# ENC_BOARD_V01.net
KiCad netlist of a schematic drawn in EAGLE
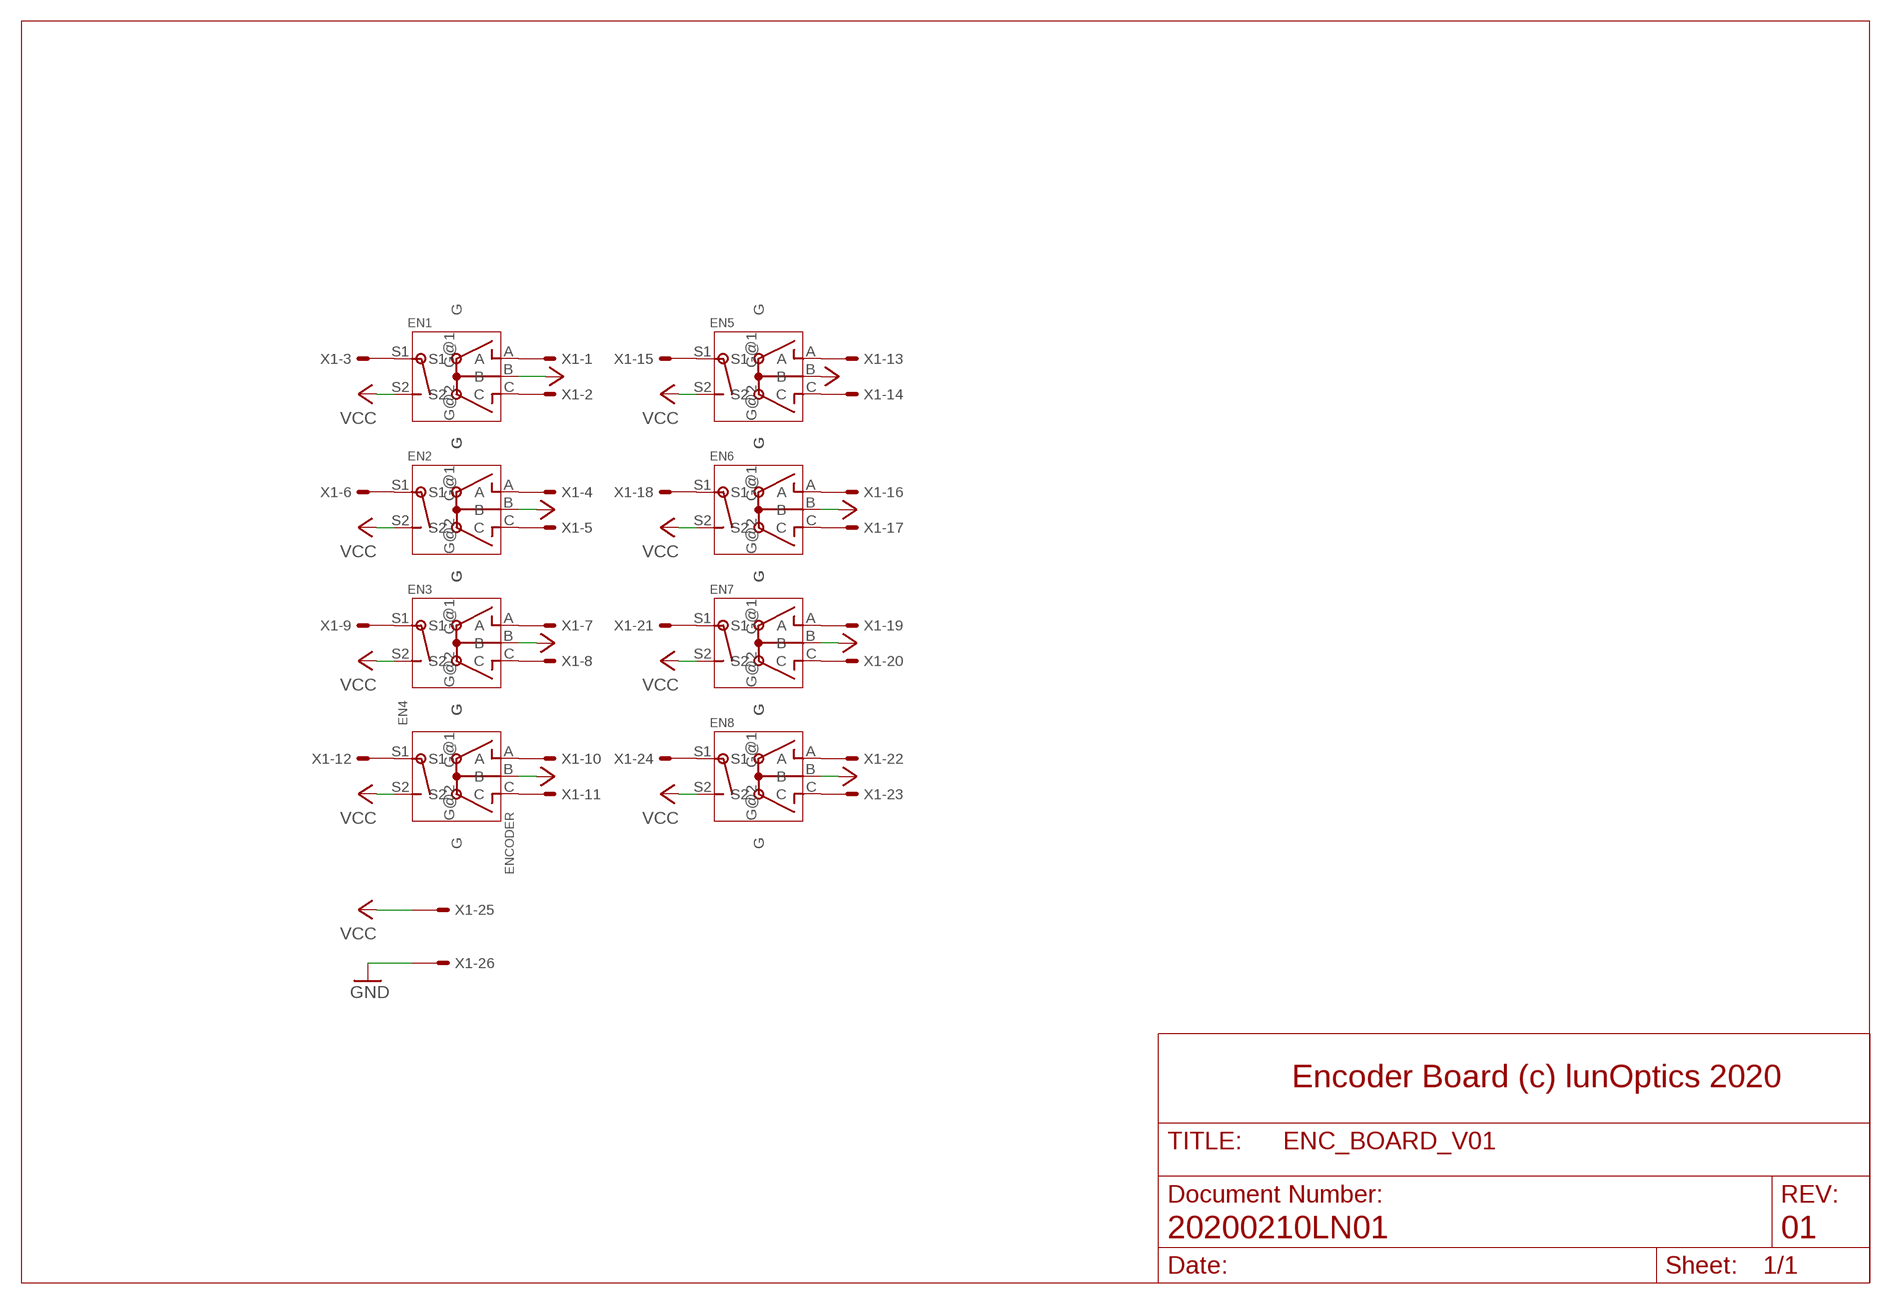
[diagram p0: schematic, sheet 1]

(export (version "E")
  (design (tool "Eeschema 10.0.6"))
  (components
    (comp (ref "EN1")
      (value "ENCODER")
      (footprint "eagle-import:ENCODER")
      (libsource (lib "eagle-import") (part "ENCODER"))
    )
    (comp (ref "EN2")
      (value "ENCODER")
      (footprint "eagle-import:ENCODER")
      (libsource (lib "eagle-import") (part "ENCODER"))
    )
    (comp (ref "EN3")
      (value "ENCODER")
      (footprint "eagle-import:ENCODER")
      (libsource (lib "eagle-import") (part "ENCODER"))
    )
    (comp (ref "EN4")
      (value "ENCODER")
      (footprint "eagle-import:ENCODER")
      (libsource (lib "eagle-import") (part "ENCODER"))
    )
    (comp (ref "EN5")
      (value "ENCODER")
      (footprint "eagle-import:ENCODER")
      (libsource (lib "eagle-import") (part "ENCODER"))
    )
    (comp (ref "EN6")
      (value "ENCODER")
      (footprint "eagle-import:ENCODER")
      (libsource (lib "eagle-import") (part "ENCODER"))
    )
    (comp (ref "EN7")
      (value "ENCODER")
      (footprint "eagle-import:ENCODER")
      (libsource (lib "eagle-import") (part "ENCODER"))
    )
    (comp (ref "EN8")
      (value "ENCODER")
      (footprint "eagle-import:ENCODER")
      (libsource (lib "eagle-import") (part "ENCODER"))
    )
    (comp (ref "X1")
      (value "057-026-1")
      (footprint "eagle-import:057-026-1")
      (libsource (lib "eagle-import") (part "057-026-1"))
    )
  )
  (nets
    (net (code "1") (name "GND") (class "Default")
      (node (ref "X1") (pin "26") (pinfunction "S_26") (pintype "passive"))
    )
    (net (code "2") (name "Net-(X1A-S)") (class "Default")
      (node (ref "EN1") (pin "A") (pinfunction "A_A") (pintype "passive"))
      (node (ref "X1") (pin "1") (pinfunction "S_1") (pintype "passive"))
    )
    (net (code "3") (name "Net-(X1B-S)") (class "Default")
      (node (ref "EN4") (pin "A") (pinfunction "A_A") (pintype "passive"))
      (node (ref "X1") (pin "10") (pinfunction "S_10") (pintype "passive"))
    )
    (net (code "4") (name "Net-(X1C-S)") (class "Default")
      (node (ref "EN4") (pin "C") (pinfunction "C_C") (pintype "passive"))
      (node (ref "X1") (pin "11") (pinfunction "S_11") (pintype "passive"))
    )
    (net (code "5") (name "Net-(X1D-S)") (class "Default")
      (node (ref "EN4") (pin "S1") (pinfunction "S1_S1") (pintype "passive"))
      (node (ref "X1") (pin "12") (pinfunction "S_12") (pintype "passive"))
    )
    (net (code "6") (name "Net-(X1E-S)") (class "Default")
      (node (ref "EN5") (pin "A") (pinfunction "A_A") (pintype "passive"))
      (node (ref "X1") (pin "13") (pinfunction "S_13") (pintype "passive"))
    )
    (net (code "7") (name "Net-(X1F-S)") (class "Default")
      (node (ref "EN5") (pin "C") (pinfunction "C_C") (pintype "passive"))
      (node (ref "X1") (pin "14") (pinfunction "S_14") (pintype "passive"))
    )
    (net (code "8") (name "Net-(X1G-S)") (class "Default")
      (node (ref "EN5") (pin "S1") (pinfunction "S1_S1") (pintype "passive"))
      (node (ref "X1") (pin "15") (pinfunction "S_15") (pintype "passive"))
    )
    (net (code "9") (name "Net-(X1H-S)") (class "Default")
      (node (ref "EN6") (pin "A") (pinfunction "A_A") (pintype "passive"))
      (node (ref "X1") (pin "16") (pinfunction "S_16") (pintype "passive"))
    )
    (net (code "10") (name "Net-(X1I-S)") (class "Default")
      (node (ref "EN6") (pin "C") (pinfunction "C_C") (pintype "passive"))
      (node (ref "X1") (pin "17") (pinfunction "S_17") (pintype "passive"))
    )
    (net (code "11") (name "Net-(X1J-S)") (class "Default")
      (node (ref "EN6") (pin "S1") (pinfunction "S1_S1") (pintype "passive"))
      (node (ref "X1") (pin "18") (pinfunction "S_18") (pintype "passive"))
    )
    (net (code "12") (name "Net-(X1K-S)") (class "Default")
      (node (ref "EN7") (pin "A") (pinfunction "A_A") (pintype "passive"))
      (node (ref "X1") (pin "19") (pinfunction "S_19") (pintype "passive"))
    )
    (net (code "13") (name "Net-(X1L-S)") (class "Default")
      (node (ref "EN1") (pin "C") (pinfunction "C_C") (pintype "passive"))
      (node (ref "X1") (pin "2") (pinfunction "S_2") (pintype "passive"))
    )
    (net (code "14") (name "Net-(X1M-S)") (class "Default")
      (node (ref "EN7") (pin "C") (pinfunction "C_C") (pintype "passive"))
      (node (ref "X1") (pin "20") (pinfunction "S_20") (pintype "passive"))
    )
    (net (code "15") (name "Net-(X1N-S)") (class "Default")
      (node (ref "EN7") (pin "S1") (pinfunction "S1_S1") (pintype "passive"))
      (node (ref "X1") (pin "21") (pinfunction "S_21") (pintype "passive"))
    )
    (net (code "16") (name "Net-(X1O-S)") (class "Default")
      (node (ref "EN8") (pin "A") (pinfunction "A_A") (pintype "passive"))
      (node (ref "X1") (pin "22") (pinfunction "S_22") (pintype "passive"))
    )
    (net (code "17") (name "Net-(X1P-S)") (class "Default")
      (node (ref "EN8") (pin "C") (pinfunction "C_C") (pintype "passive"))
      (node (ref "X1") (pin "23") (pinfunction "S_23") (pintype "passive"))
    )
    (net (code "18") (name "Net-(X1Q-S)") (class "Default")
      (node (ref "EN8") (pin "S1") (pinfunction "S1_S1") (pintype "passive"))
      (node (ref "X1") (pin "24") (pinfunction "S_24") (pintype "passive"))
    )
    (net (code "19") (name "Net-(X1T-S)") (class "Default")
      (node (ref "EN1") (pin "S1") (pinfunction "S1_S1") (pintype "passive"))
      (node (ref "X1") (pin "3") (pinfunction "S_3") (pintype "passive"))
    )
    (net (code "20") (name "Net-(X1U-S)") (class "Default")
      (node (ref "EN2") (pin "A") (pinfunction "A_A") (pintype "passive"))
      (node (ref "X1") (pin "4") (pinfunction "S_4") (pintype "passive"))
    )
    (net (code "21") (name "Net-(X1V-S)") (class "Default")
      (node (ref "EN2") (pin "C") (pinfunction "C_C") (pintype "passive"))
      (node (ref "X1") (pin "5") (pinfunction "S_5") (pintype "passive"))
    )
    (net (code "22") (name "Net-(X1W-S)") (class "Default")
      (node (ref "EN2") (pin "S1") (pinfunction "S1_S1") (pintype "passive"))
      (node (ref "X1") (pin "6") (pinfunction "S_6") (pintype "passive"))
    )
    (net (code "23") (name "Net-(X1X-S)") (class "Default")
      (node (ref "EN3") (pin "A") (pinfunction "A_A") (pintype "passive"))
      (node (ref "X1") (pin "7") (pinfunction "S_7") (pintype "passive"))
    )
    (net (code "24") (name "Net-(X1Y-S)") (class "Default")
      (node (ref "EN3") (pin "C") (pinfunction "C_C") (pintype "passive"))
      (node (ref "X1") (pin "8") (pinfunction "S_8") (pintype "passive"))
    )
    (net (code "25") (name "Net-(X1Z-S)") (class "Default")
      (node (ref "EN3") (pin "S1") (pinfunction "S1_S1") (pintype "passive"))
      (node (ref "X1") (pin "9") (pinfunction "S_9") (pintype "passive"))
    )
    (net (code "26") (name "VCC") (class "Default")
      (node (ref "EN1") (pin "B") (pinfunction "B_B") (pintype "passive"))
      (node (ref "EN1") (pin "S2") (pinfunction "S2_S2") (pintype "passive"))
      (node (ref "EN2") (pin "B") (pinfunction "B_B") (pintype "passive"))
      (node (ref "EN2") (pin "S2") (pinfunction "S2_S2") (pintype "passive"))
      (node (ref "EN3") (pin "B") (pinfunction "B_B") (pintype "passive"))
      (node (ref "EN3") (pin "S2") (pinfunction "S2_S2") (pintype "passive"))
      (node (ref "EN4") (pin "B") (pinfunction "B_B") (pintype "passive"))
      (node (ref "EN4") (pin "S2") (pinfunction "S2_S2") (pintype "passive"))
      (node (ref "EN5") (pin "B") (pinfunction "B_B") (pintype "passive"))
      (node (ref "EN5") (pin "S2") (pinfunction "S2_S2") (pintype "passive"))
      (node (ref "EN6") (pin "B") (pinfunction "B_B") (pintype "passive"))
      (node (ref "EN6") (pin "S2") (pinfunction "S2_S2") (pintype "passive"))
      (node (ref "EN7") (pin "B") (pinfunction "B_B") (pintype "passive"))
      (node (ref "EN7") (pin "S2") (pinfunction "S2_S2") (pintype "passive"))
      (node (ref "EN8") (pin "B") (pinfunction "B_B") (pintype "passive"))
      (node (ref "EN8") (pin "S2") (pinfunction "S2_S2") (pintype "passive"))
      (node (ref "X1") (pin "25") (pinfunction "S_25") (pintype "passive"))
    )
    (net (code "27") (name "unconnected-(EN1-G-PadG@1)") (class "Default")
      (node (ref "EN1") (pin "G@1") (pinfunction "G_G@1") (pintype "passive"))
    )
    (net (code "28") (name "unconnected-(EN1-G-PadG@2)") (class "Default")
      (node (ref "EN1") (pin "G@2") (pinfunction "G_G@2") (pintype "passive"))
    )
    (net (code "29") (name "unconnected-(EN2-G-PadG@1)") (class "Default")
      (node (ref "EN2") (pin "G@1") (pinfunction "G_G@1") (pintype "passive"))
    )
    (net (code "30") (name "unconnected-(EN2-G-PadG@2)") (class "Default")
      (node (ref "EN2") (pin "G@2") (pinfunction "G_G@2") (pintype "passive"))
    )
    (net (code "31") (name "unconnected-(EN3-G-PadG@1)") (class "Default")
      (node (ref "EN3") (pin "G@1") (pinfunction "G_G@1") (pintype "passive"))
    )
    (net (code "32") (name "unconnected-(EN3-G-PadG@2)") (class "Default")
      (node (ref "EN3") (pin "G@2") (pinfunction "G_G@2") (pintype "passive"))
    )
    (net (code "33") (name "unconnected-(EN4-G-PadG@1)") (class "Default")
      (node (ref "EN4") (pin "G@1") (pinfunction "G_G@1") (pintype "passive"))
    )
    (net (code "34") (name "unconnected-(EN4-G-PadG@2)") (class "Default")
      (node (ref "EN4") (pin "G@2") (pinfunction "G_G@2") (pintype "passive"))
    )
    (net (code "35") (name "unconnected-(EN5-G-PadG@1)") (class "Default")
      (node (ref "EN5") (pin "G@1") (pinfunction "G_G@1") (pintype "passive"))
    )
    (net (code "36") (name "unconnected-(EN5-G-PadG@2)") (class "Default")
      (node (ref "EN5") (pin "G@2") (pinfunction "G_G@2") (pintype "passive"))
    )
    (net (code "37") (name "unconnected-(EN6-G-PadG@1)") (class "Default")
      (node (ref "EN6") (pin "G@1") (pinfunction "G_G@1") (pintype "passive"))
    )
    (net (code "38") (name "unconnected-(EN6-G-PadG@2)") (class "Default")
      (node (ref "EN6") (pin "G@2") (pinfunction "G_G@2") (pintype "passive"))
    )
    (net (code "39") (name "unconnected-(EN7-G-PadG@1)") (class "Default")
      (node (ref "EN7") (pin "G@1") (pinfunction "G_G@1") (pintype "passive"))
    )
    (net (code "40") (name "unconnected-(EN7-G-PadG@2)") (class "Default")
      (node (ref "EN7") (pin "G@2") (pinfunction "G_G@2") (pintype "passive"))
    )
    (net (code "41") (name "unconnected-(EN8-G-PadG@1)") (class "Default")
      (node (ref "EN8") (pin "G@1") (pinfunction "G_G@1") (pintype "passive"))
    )
    (net (code "42") (name "unconnected-(EN8-G-PadG@2)") (class "Default")
      (node (ref "EN8") (pin "G@2") (pinfunction "G_G@2") (pintype "passive"))
    )
  )
)
